# ESP8266.net
KiCad netlist of a schematic drawn in Altium Designer
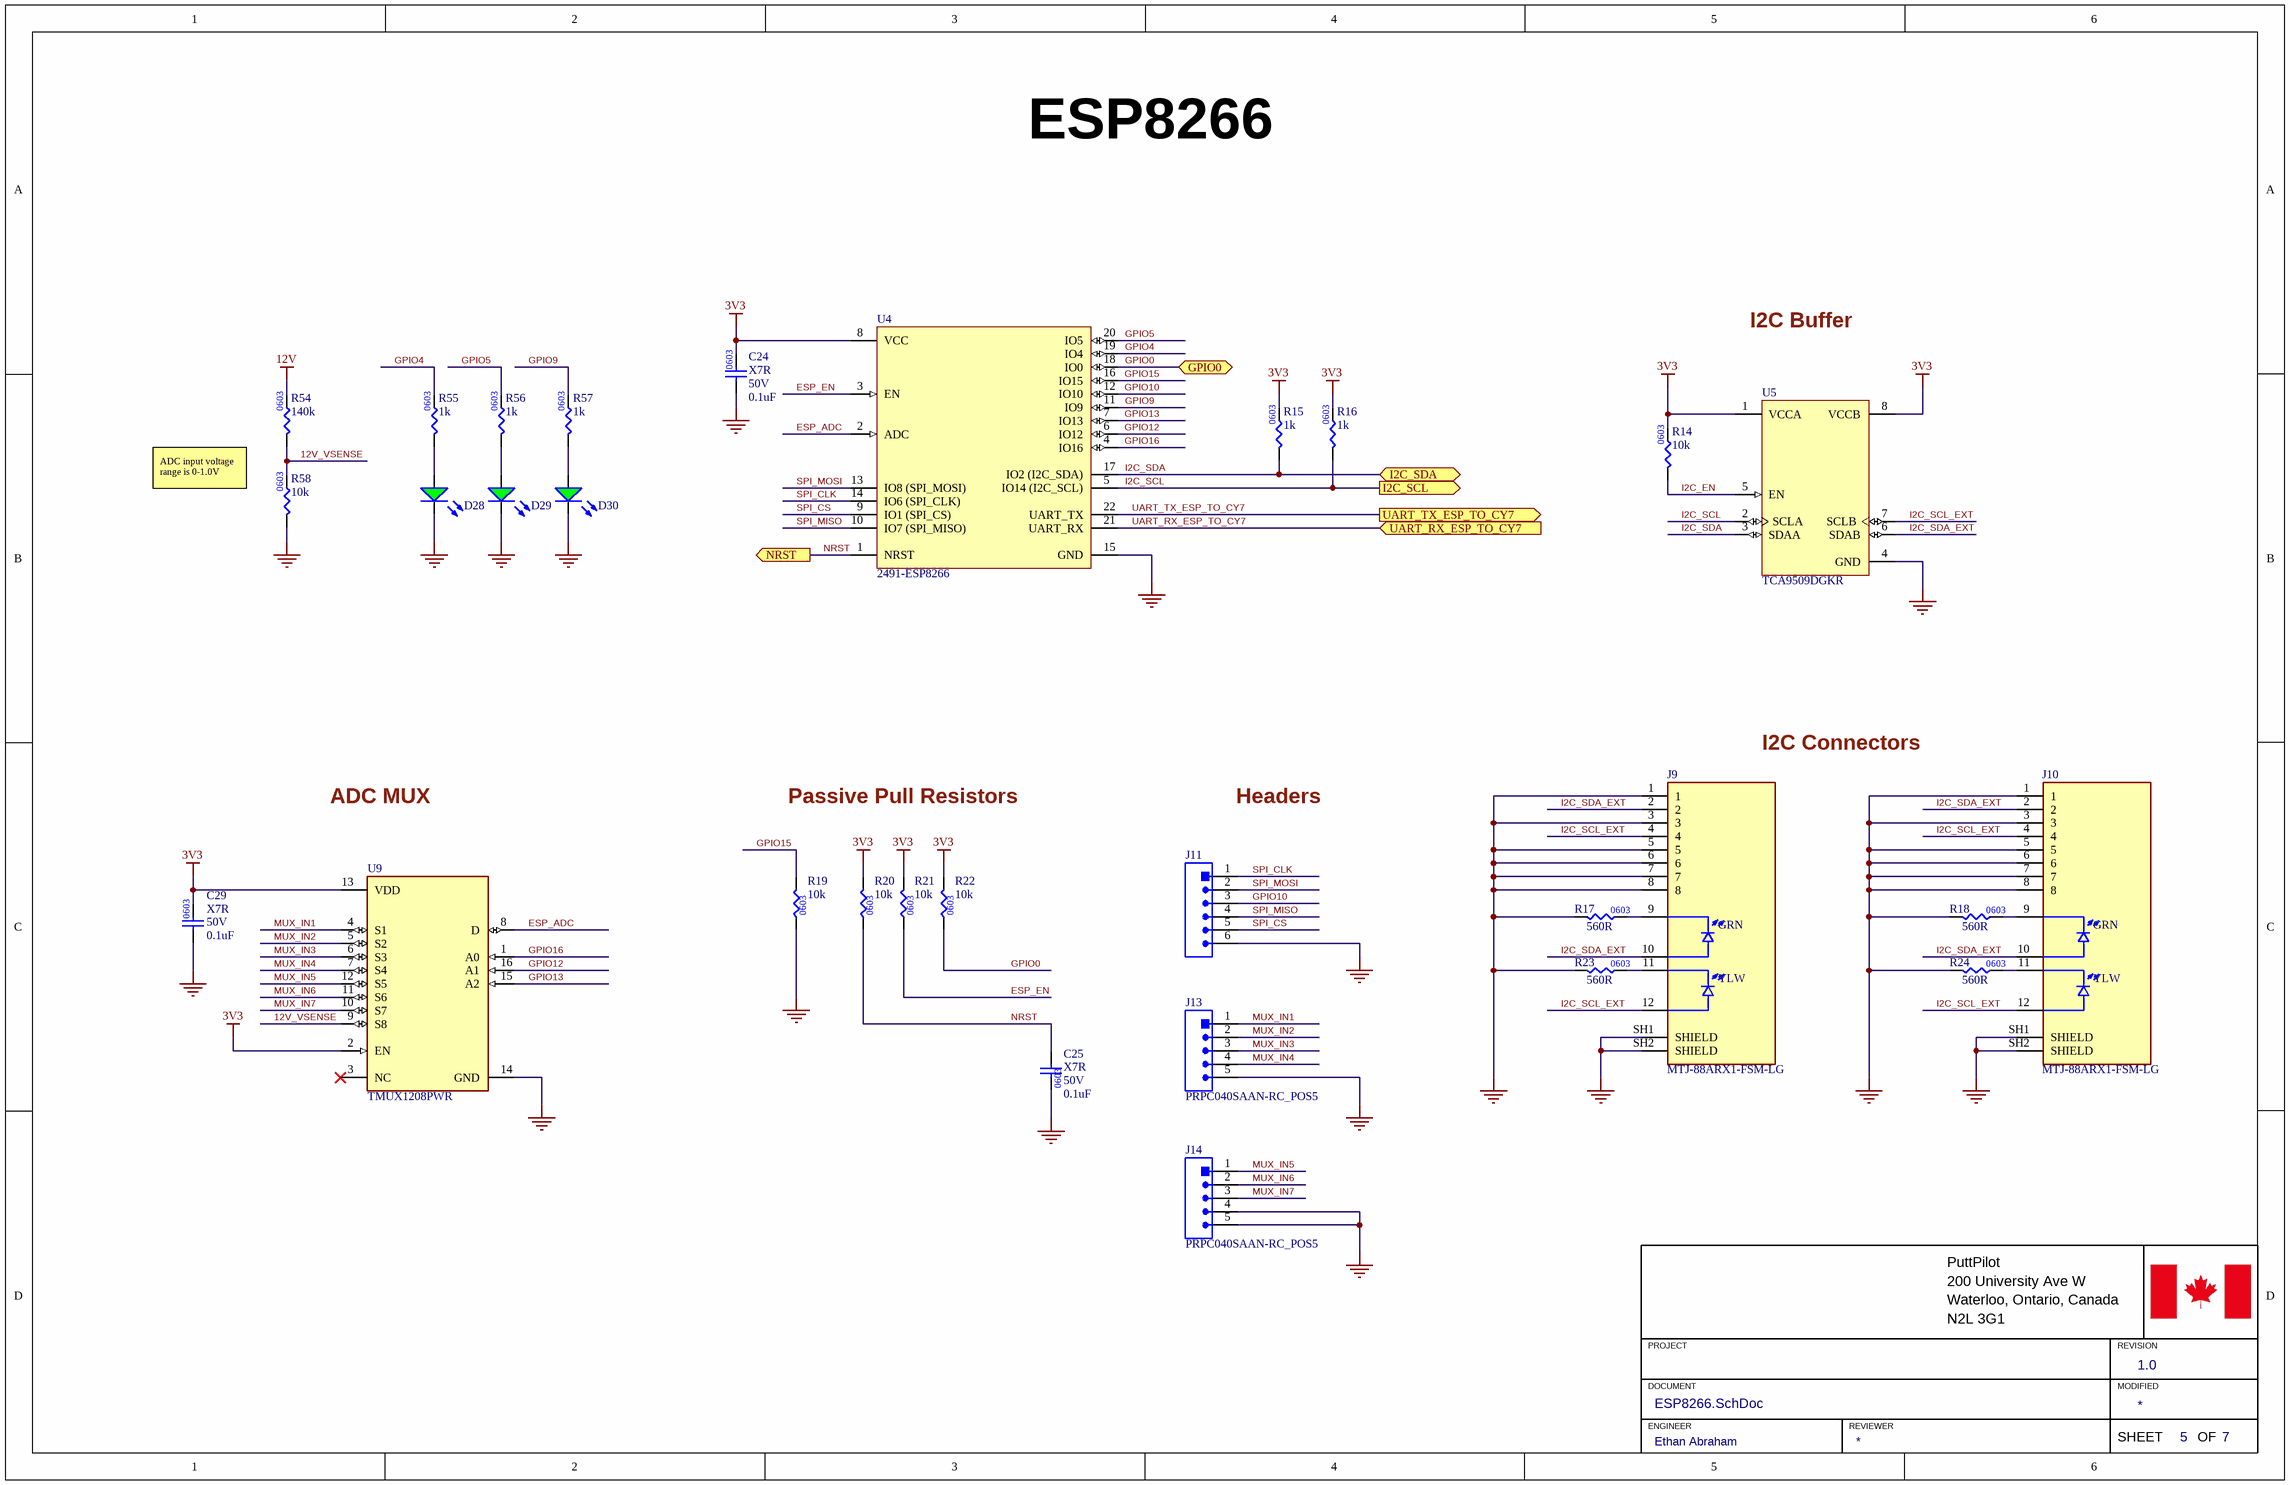
[diagram p0: ESP8266.SchDoc]

(export (version "E")
  (design (tool "Eeschema 10.0.6"))
  (components
    (comp (ref "C24")
      (value "GCJ188R71H104KA12D")
      (footprint ".CAP_0603")
      (description "CAP CER 0.1uF 50V X7R 0603")
      (fields
        (field (name "MANUFACTURER") "Murata")
        (field (name "TEMPERATURE CHARACTERISTICS CODE") "X7R")
        (field (name "RATED DC VOLTAGE (URDC)") "50V")
        (field (name "CAPACITANCE") "0.1uF")
      )
      (libsource (lib "PuttPilot") (part "GCJ188R71H104KA12D"))
    )
    (comp (ref "C25")
      (value "GCJ188R71H104KA12D")
      (footprint ".CAP_0603")
      (description "CAP CER 0.1uF 50V X7R 0603")
      (fields
        (field (name "MANUFACTURER") "Murata")
        (field (name "TEMPERATURE CHARACTERISTICS CODE") "X7R")
        (field (name "RATED DC VOLTAGE (URDC)") "50V")
        (field (name "CAPACITANCE") "0.1uF")
      )
      (libsource (lib "PuttPilot") (part "GCJ188R71H104KA12D"))
    )
    (comp (ref "C29")
      (value "GCJ188R71H104KA12D")
      (footprint ".CAP_0603")
      (description "CAP CER 0.1uF 50V X7R 0603")
      (fields
        (field (name "MANUFACTURER") "Murata")
        (field (name "TEMPERATURE CHARACTERISTICS CODE") "X7R")
        (field (name "RATED DC VOLTAGE (URDC)") "50V")
        (field (name "CAPACITANCE") "0.1uF")
      )
      (libsource (lib "PuttPilot") (part "GCJ188R71H104KA12D"))
    )
    (comp (ref "D28")
      (value "LTST-C191KGKT")
      (footprint ".LED_0603")
      (description "LED GREEN 2V 0603")
      (fields (field (name "MANUFACTURER") "Vishay Lite-On"))
      (libsource (lib "PuttPilot") (part "LTST-C191KGKT"))
    )
    (comp (ref "D29")
      (value "LTST-C191KGKT")
      (footprint ".LED_0603")
      (description "LED GREEN 2V 0603")
      (fields (field (name "MANUFACTURER") "Vishay Lite-On"))
      (libsource (lib "PuttPilot") (part "LTST-C191KGKT"))
    )
    (comp (ref "D30")
      (value "LTST-C191KGKT")
      (footprint ".LED_0603")
      (description "LED GREEN 2V 0603")
      (fields (field (name "MANUFACTURER") "Vishay Lite-On"))
      (libsource (lib "PuttPilot") (part "LTST-C191KGKT"))
    )
    (comp (ref "J9")
      (value "MTJ-88ARX1-FSM-LG")
      (footprint "MTJ-88ARX1-FSM-LG")
      (description "RJ45 JACK R/A SHIELDED")
      (fields (field (name "MANUFACTURER") "Adam Equipment"))
      (libsource (lib "PuttPilot") (part "MTJ-88ARX1-FSM-LG"))
    )
    (comp (ref "J10")
      (value "MTJ-88ARX1-FSM-LG")
      (footprint "MTJ-88ARX1-FSM-LG")
      (description "RJ45 JACK R/A SHIELDED")
      (fields (field (name "MANUFACTURER") "Adam Equipment"))
      (libsource (lib "PuttPilot") (part "MTJ-88ARX1-FSM-LG"))
    )
    (comp (ref "J11")
      (value "PRPC040SAAN-RC_POS6")
      (footprint "HEADER_6POS_2.54MM")
      (description "CONN HEADER VERT 6POS 2.54MM")
      (libsource (lib "PuttPilot") (part "PRPC040SAAN-RC_POS6"))
    )
    (comp (ref "J13")
      (value "PRPC040SAAN-RC_POS5")
      (footprint "HEADER_5POS_2.54MM")
      (description "CONN HEADER VERT 5POS 2.54MM")
      (libsource (lib "PuttPilot") (part "PRPC040SAAN-RC_POS5"))
    )
    (comp (ref "J14")
      (value "PRPC040SAAN-RC_POS5")
      (footprint "HEADER_5POS_2.54MM")
      (description "CONN HEADER VERT 5POS 2.54MM")
      (libsource (lib "PuttPilot") (part "PRPC040SAAN-RC_POS5"))
    )
    (comp (ref "R14")
      (value "RC0603FR-0710KL")
      (footprint ".RES_0603")
      (description "RES 10K OHM 0603")
      (fields
        (field (name "MANUFACTURER") "Yageo")
        (field (name "TOLERANCE") "1%")
        (field (name "RESISTANCE") "10k")
      )
      (libsource (lib "PuttPilot") (part "RC0603FR-0710KL"))
    )
    (comp (ref "R15")
      (value "RC0603FR-071KL")
      (footprint ".RES_0603")
      (description "RES 1K OHM 0603")
      (fields
        (field (name "MANUFACTURER") "Yageo")
        (field (name "TOLERANCE") "1%")
        (field (name "RESISTANCE") "1k")
      )
      (libsource (lib "PuttPilot") (part "RC0603FR-071KL"))
    )
    (comp (ref "R16")
      (value "RC0603FR-071KL")
      (footprint ".RES_0603")
      (description "RES 1K OHM 0603")
      (fields
        (field (name "MANUFACTURER") "Yageo")
        (field (name "TOLERANCE") "1%")
        (field (name "RESISTANCE") "1k")
      )
      (libsource (lib "PuttPilot") (part "RC0603FR-071KL"))
    )
    (comp (ref "R17")
      (value "RC0603FR-07560RL")
      (footprint ".RES_0603")
      (description "RES 560 OHM 0603")
      (fields
        (field (name "MANUFACTURER") "Yageo")
        (field (name "TOLERANCE") "1%")
        (field (name "RESISTANCE") "560R")
      )
      (libsource (lib "PuttPilot") (part "RC0603FR-07560RL"))
    )
    (comp (ref "R18")
      (value "RC0603FR-07560RL")
      (footprint ".RES_0603")
      (description "RES 560 OHM 0603")
      (fields
        (field (name "MANUFACTURER") "Yageo")
        (field (name "TOLERANCE") "1%")
        (field (name "RESISTANCE") "560R")
      )
      (libsource (lib "PuttPilot") (part "RC0603FR-07560RL"))
    )
    (comp (ref "R19")
      (value "RC0603FR-0710KL")
      (footprint ".RES_0603")
      (description "RES 10K OHM 0603")
      (fields
        (field (name "MANUFACTURER") "Yageo")
        (field (name "TOLERANCE") "1%")
        (field (name "RESISTANCE") "10k")
      )
      (libsource (lib "PuttPilot") (part "RC0603FR-0710KL"))
    )
    (comp (ref "R20")
      (value "RC0603FR-0710KL")
      (footprint ".RES_0603")
      (description "RES 10K OHM 0603")
      (fields
        (field (name "MANUFACTURER") "Yageo")
        (field (name "TOLERANCE") "1%")
        (field (name "RESISTANCE") "10k")
      )
      (libsource (lib "PuttPilot") (part "RC0603FR-0710KL"))
    )
    (comp (ref "R21")
      (value "RC0603FR-0710KL")
      (footprint ".RES_0603")
      (description "RES 10K OHM 0603")
      (fields
        (field (name "MANUFACTURER") "Yageo")
        (field (name "TOLERANCE") "1%")
        (field (name "RESISTANCE") "10k")
      )
      (libsource (lib "PuttPilot") (part "RC0603FR-0710KL"))
    )
    (comp (ref "R22")
      (value "RC0603FR-0710KL")
      (footprint ".RES_0603")
      (description "RES 10K OHM 0603")
      (fields
        (field (name "MANUFACTURER") "Yageo")
        (field (name "TOLERANCE") "1%")
        (field (name "RESISTANCE") "10k")
      )
      (libsource (lib "PuttPilot") (part "RC0603FR-0710KL"))
    )
    (comp (ref "R23")
      (value "RC0603FR-07560RL")
      (footprint ".RES_0603")
      (description "RES 560 OHM 0603")
      (fields
        (field (name "MANUFACTURER") "Yageo")
        (field (name "TOLERANCE") "1%")
        (field (name "RESISTANCE") "560R")
      )
      (libsource (lib "PuttPilot") (part "RC0603FR-07560RL"))
    )
    (comp (ref "R24")
      (value "RC0603FR-07560RL")
      (footprint ".RES_0603")
      (description "RES 560 OHM 0603")
      (fields
        (field (name "MANUFACTURER") "Yageo")
        (field (name "TOLERANCE") "1%")
        (field (name "RESISTANCE") "560R")
      )
      (libsource (lib "PuttPilot") (part "RC0603FR-07560RL"))
    )
    (comp (ref "R54")
      (value "RC0603FR-07140KL")
      (footprint ".RES_0603")
      (description "RES 140K OHM 0603")
      (fields
        (field (name "MANUFACTURER") "Yageo")
        (field (name "TOLERANCE") "1%")
        (field (name "RESISTANCE") "140k")
      )
      (libsource (lib "PuttPilot") (part "RC0603FR-07140KL"))
    )
    (comp (ref "R55")
      (value "RC0603FR-071KL")
      (footprint ".RES_0603")
      (description "RES 1K OHM 0603")
      (fields
        (field (name "MANUFACTURER") "Yageo")
        (field (name "TOLERANCE") "1%")
        (field (name "RESISTANCE") "1k")
      )
      (libsource (lib "PuttPilot") (part "RC0603FR-071KL"))
    )
    (comp (ref "R56")
      (value "RC0603FR-071KL")
      (footprint ".RES_0603")
      (description "RES 1K OHM 0603")
      (fields
        (field (name "MANUFACTURER") "Yageo")
        (field (name "TOLERANCE") "1%")
        (field (name "RESISTANCE") "1k")
      )
      (libsource (lib "PuttPilot") (part "RC0603FR-071KL"))
    )
    (comp (ref "R57")
      (value "RC0603FR-071KL")
      (footprint ".RES_0603")
      (description "RES 1K OHM 0603")
      (fields
        (field (name "MANUFACTURER") "Yageo")
        (field (name "TOLERANCE") "1%")
        (field (name "RESISTANCE") "1k")
      )
      (libsource (lib "PuttPilot") (part "RC0603FR-071KL"))
    )
    (comp (ref "R58")
      (value "RC0603FR-0710KL")
      (footprint ".RES_0603")
      (description "RES 10K OHM 0603")
      (fields
        (field (name "MANUFACTURER") "Yageo")
        (field (name "TOLERANCE") "1%")
        (field (name "RESISTANCE") "10k")
      )
      (libsource (lib "PuttPilot") (part "RC0603FR-0710KL"))
    )
    (comp (ref "U4")
      (value "2491-ESP8266")
      (footprint "2491-ESP8266")
      (description "ESP8266 + Trace Antenna, 4MB Flash")
      (libsource (lib "PuttPilot") (part "2491-ESP8266"))
    )
    (comp (ref "U5")
      (value "TCA9509DGKR")
      (footprint "TCA9509DGKR")
      (description "I2C BUFFER IC")
      (fields (field (name "MANUFACTURER") "Texas Instruments"))
      (libsource (lib "PuttPilot") (part "TCA9509DGKR"))
    )
    (comp (ref "U9")
      (value "TMUX1208PWR")
      (footprint "TMUX1208")
      (description "Single-Ended Multiplexer, 1 Func, 8 Channel, CMOS, PDSO16")
      (fields (field (name "MANUFACTURER") "Texas Instruments"))
      (libsource (lib "PuttPilot") (part "TMUX1208PWR"))
    )
  )
  (nets
    (net (code "1") (name "/12V_VSENSE") (class "Default")
      (node (ref "R54") (pin "1") (pinfunction "1_1") (pintype "passive"))
      (node (ref "R58") (pin "2") (pinfunction "2_2") (pintype "passive"))
      (node (ref "U9") (pin "9") (pinfunction "S8_9") (pintype "bidirectional"))
    )
    (net (code "2") (name "/ESP_ADC") (class "Default")
      (node (ref "U4") (pin "2") (pinfunction "ADC_2") (pintype "input"))
      (node (ref "U9") (pin "8") (pinfunction "D_8") (pintype "bidirectional"))
    )
    (net (code "3") (name "/ESP_EN") (class "Default")
      (node (ref "R21") (pin "1") (pinfunction "1_1") (pintype "passive"))
      (node (ref "U4") (pin "3") (pinfunction "EN_3") (pintype "input"))
    )
    (net (code "4") (name "/GPIO0") (class "Default")
      (node (ref "R22") (pin "1") (pinfunction "1_1") (pintype "passive"))
      (node (ref "U4") (pin "18") (pinfunction "IO0_18") (pintype "bidirectional"))
    )
    (net (code "5") (name "/GPIO4") (class "Default")
      (node (ref "R55") (pin "2") (pinfunction "2_2") (pintype "passive"))
      (node (ref "U4") (pin "19") (pinfunction "IO4_19") (pintype "bidirectional"))
    )
    (net (code "6") (name "/GPIO5") (class "Default")
      (node (ref "R56") (pin "2") (pinfunction "2_2") (pintype "passive"))
      (node (ref "U4") (pin "20") (pinfunction "IO5_20") (pintype "bidirectional"))
    )
    (net (code "7") (name "/GPIO9") (class "Default")
      (node (ref "R57") (pin "2") (pinfunction "2_2") (pintype "passive"))
      (node (ref "U4") (pin "11") (pinfunction "IO9_11") (pintype "bidirectional"))
    )
    (net (code "8") (name "/GPIO10") (class "Default")
      (node (ref "J11") (pin "3") (pinfunction "3_3") (pintype "passive"))
      (node (ref "U4") (pin "12") (pinfunction "IO10_12") (pintype "bidirectional"))
    )
    (net (code "9") (name "/GPIO12") (class "Default")
      (node (ref "U4") (pin "6") (pinfunction "IO12_6") (pintype "bidirectional"))
      (node (ref "U9") (pin "16") (pinfunction "A1_16") (pintype "input"))
    )
    (net (code "10") (name "/GPIO13") (class "Default")
      (node (ref "U4") (pin "7") (pinfunction "IO13_7") (pintype "bidirectional"))
      (node (ref "U9") (pin "15") (pinfunction "A2_15") (pintype "input"))
    )
    (net (code "11") (name "/GPIO15") (class "Default")
      (node (ref "R19") (pin "2") (pinfunction "2_2") (pintype "passive"))
      (node (ref "U4") (pin "16") (pinfunction "IO15_16") (pintype "bidirectional"))
    )
    (net (code "12") (name "/GPIO16") (class "Default")
      (node (ref "U4") (pin "4") (pinfunction "IO16_4") (pintype "bidirectional"))
      (node (ref "U9") (pin "1") (pinfunction "A0_1") (pintype "input"))
    )
    (net (code "13") (name "/I2C_EN") (class "Default")
      (node (ref "R14") (pin "1") (pinfunction "1_1") (pintype "passive"))
      (node (ref "U5") (pin "5") (pinfunction "EN_5") (pintype "input"))
    )
    (net (code "14") (name "/I2C_SCL") (class "Default")
      (node (ref "R16") (pin "1") (pinfunction "1_1") (pintype "passive"))
      (node (ref "U4") (pin "5") (pinfunction "IO14_(I2C_SCL)_5") (pintype "passive"))
      (node (ref "U5") (pin "2") (pinfunction "SCLA_2") (pintype "bidirectional"))
    )
    (net (code "15") (name "/I2C_SCL_EXT") (class "Default")
      (node (ref "J10") (pin "12") (pinfunction "12_12") (pintype "passive"))
      (node (ref "J10") (pin "4") (pinfunction "4_4") (pintype "passive"))
      (node (ref "J9") (pin "12") (pinfunction "12_12") (pintype "passive"))
      (node (ref "J9") (pin "4") (pinfunction "4_4") (pintype "passive"))
      (node (ref "U5") (pin "7") (pinfunction "SCLB_7") (pintype "bidirectional"))
    )
    (net (code "16") (name "/I2C_SDA") (class "Default")
      (node (ref "R15") (pin "1") (pinfunction "1_1") (pintype "passive"))
      (node (ref "U4") (pin "17") (pinfunction "IO2_(I2C_SDA)_17") (pintype "passive"))
      (node (ref "U5") (pin "3") (pinfunction "SDAA_3") (pintype "bidirectional"))
    )
    (net (code "17") (name "/I2C_SDA_EXT") (class "Default")
      (node (ref "J10") (pin "10") (pinfunction "10_10") (pintype "passive"))
      (node (ref "J10") (pin "2") (pinfunction "2_2") (pintype "passive"))
      (node (ref "J9") (pin "10") (pinfunction "10_10") (pintype "passive"))
      (node (ref "J9") (pin "2") (pinfunction "2_2") (pintype "passive"))
      (node (ref "U5") (pin "6") (pinfunction "SDAB_6") (pintype "bidirectional"))
    )
    (net (code "18") (name "/MUX_IN1") (class "Default")
      (node (ref "J13") (pin "1") (pinfunction "1_1") (pintype "passive"))
      (node (ref "U9") (pin "4") (pinfunction "S1_4") (pintype "bidirectional"))
    )
    (net (code "19") (name "/MUX_IN2") (class "Default")
      (node (ref "J13") (pin "2") (pinfunction "2_2") (pintype "passive"))
      (node (ref "U9") (pin "5") (pinfunction "S2_5") (pintype "bidirectional"))
    )
    (net (code "20") (name "/MUX_IN3") (class "Default")
      (node (ref "J13") (pin "3") (pinfunction "3_3") (pintype "passive"))
      (node (ref "U9") (pin "6") (pinfunction "S3_6") (pintype "bidirectional"))
    )
    (net (code "21") (name "/MUX_IN4") (class "Default")
      (node (ref "J13") (pin "4") (pinfunction "4_4") (pintype "passive"))
      (node (ref "U9") (pin "7") (pinfunction "S4_7") (pintype "bidirectional"))
    )
    (net (code "22") (name "/MUX_IN5") (class "Default")
      (node (ref "J14") (pin "1") (pinfunction "1_1") (pintype "passive"))
      (node (ref "U9") (pin "12") (pinfunction "S5_12") (pintype "bidirectional"))
    )
    (net (code "23") (name "/MUX_IN6") (class "Default")
      (node (ref "J14") (pin "2") (pinfunction "2_2") (pintype "passive"))
      (node (ref "U9") (pin "11") (pinfunction "S6_11") (pintype "bidirectional"))
    )
    (net (code "24") (name "/MUX_IN7") (class "Default")
      (node (ref "J14") (pin "3") (pinfunction "3_3") (pintype "passive"))
      (node (ref "U9") (pin "10") (pinfunction "S7_10") (pintype "bidirectional"))
    )
    (net (code "25") (name "/NRST") (class "Default")
      (node (ref "C25") (pin "2") (pinfunction "2_2") (pintype "passive"))
      (node (ref "R20") (pin "1") (pinfunction "1_1") (pintype "passive"))
      (node (ref "U4") (pin "1") (pinfunction "NRST_1") (pintype "passive"))
    )
    (net (code "26") (name "/SPI_CLK") (class "Default")
      (node (ref "J11") (pin "1") (pinfunction "1_1") (pintype "passive"))
      (node (ref "U4") (pin "14") (pinfunction "IO6_(SPI_CLK)_14") (pintype "passive"))
    )
    (net (code "27") (name "/SPI_CS") (class "Default")
      (node (ref "J11") (pin "5") (pinfunction "5_5") (pintype "passive"))
      (node (ref "U4") (pin "9") (pinfunction "IO1_(SPI_CS)_9") (pintype "passive"))
    )
    (net (code "28") (name "/SPI_MISO") (class "Default")
      (node (ref "J11") (pin "4") (pinfunction "4_4") (pintype "passive"))
      (node (ref "U4") (pin "10") (pinfunction "IO7_(SPI_MISO)_10") (pintype "passive"))
    )
    (net (code "29") (name "/SPI_MOSI") (class "Default")
      (node (ref "J11") (pin "2") (pinfunction "2_2") (pintype "passive"))
      (node (ref "U4") (pin "13") (pinfunction "IO8_(SPI_MOSI)_13") (pintype "passive"))
    )
    (net (code "30") (name "/UART_RX_ESP_TO_CY7") (class "Default")
      (node (ref "U4") (pin "21") (pinfunction "UART_RX_21") (pintype "passive"))
    )
    (net (code "31") (name "/UART_TX_ESP_TO_CY7") (class "Default")
      (node (ref "U4") (pin "22") (pinfunction "UART_TX_22") (pintype "passive"))
    )
    (net (code "32") (name "3V3") (class "Default")
      (node (ref "C24") (pin "2") (pinfunction "2_2") (pintype "passive"))
      (node (ref "C29") (pin "2") (pinfunction "2_2") (pintype "passive"))
      (node (ref "R14") (pin "2") (pinfunction "2_2") (pintype "passive"))
      (node (ref "R15") (pin "2") (pinfunction "2_2") (pintype "passive"))
      (node (ref "R16") (pin "2") (pinfunction "2_2") (pintype "passive"))
      (node (ref "R20") (pin "2") (pinfunction "2_2") (pintype "passive"))
      (node (ref "R21") (pin "2") (pinfunction "2_2") (pintype "passive"))
      (node (ref "R22") (pin "2") (pinfunction "2_2") (pintype "passive"))
      (node (ref "U4") (pin "8") (pinfunction "VCC_8") (pintype "power_in"))
      (node (ref "U5") (pin "1") (pinfunction "VCCA_1") (pintype "power_in"))
      (node (ref "U5") (pin "8") (pinfunction "VCCB_8") (pintype "power_in"))
      (node (ref "U9") (pin "13") (pinfunction "VDD_13") (pintype "power_in"))
      (node (ref "U9") (pin "2") (pinfunction "EN_2") (pintype "input"))
    )
    (net (code "33") (name "12V") (class "Default")
      (node (ref "R54") (pin "2") (pinfunction "2_2") (pintype "passive"))
    )
    (net (code "34") (name "GND") (class "Default")
      (node (ref "C24") (pin "1") (pinfunction "1_1") (pintype "passive"))
      (node (ref "C25") (pin "1") (pinfunction "1_1") (pintype "passive"))
      (node (ref "C29") (pin "1") (pinfunction "1_1") (pintype "passive"))
      (node (ref "D28") (pin "2") (pinfunction "K_2") (pintype "passive"))
      (node (ref "D29") (pin "2") (pinfunction "K_2") (pintype "passive"))
      (node (ref "D30") (pin "2") (pinfunction "K_2") (pintype "passive"))
      (node (ref "J10") (pin "1") (pinfunction "1_1") (pintype "passive"))
      (node (ref "J10") (pin "3") (pinfunction "3_3") (pintype "passive"))
      (node (ref "J10") (pin "5") (pinfunction "5_5") (pintype "passive"))
      (node (ref "J10") (pin "6") (pinfunction "6_6") (pintype "passive"))
      (node (ref "J10") (pin "7") (pinfunction "7_7") (pintype "passive"))
      (node (ref "J10") (pin "8") (pinfunction "8_8") (pintype "passive"))
      (node (ref "J10") (pin "SH1") (pinfunction "SHIELD_SH1") (pintype "passive"))
      (node (ref "J10") (pin "SH2") (pinfunction "SHIELD_SH2") (pintype "passive"))
      (node (ref "J11") (pin "6") (pinfunction "6_6") (pintype "passive"))
      (node (ref "J13") (pin "5") (pinfunction "5_5") (pintype "passive"))
      (node (ref "J14") (pin "4") (pinfunction "4_4") (pintype "passive"))
      (node (ref "J14") (pin "5") (pinfunction "5_5") (pintype "passive"))
      (node (ref "J9") (pin "1") (pinfunction "1_1") (pintype "passive"))
      (node (ref "J9") (pin "3") (pinfunction "3_3") (pintype "passive"))
      (node (ref "J9") (pin "5") (pinfunction "5_5") (pintype "passive"))
      (node (ref "J9") (pin "6") (pinfunction "6_6") (pintype "passive"))
      (node (ref "J9") (pin "7") (pinfunction "7_7") (pintype "passive"))
      (node (ref "J9") (pin "8") (pinfunction "8_8") (pintype "passive"))
      (node (ref "J9") (pin "SH1") (pinfunction "SHIELD_SH1") (pintype "passive"))
      (node (ref "J9") (pin "SH2") (pinfunction "SHIELD_SH2") (pintype "passive"))
      (node (ref "R17") (pin "1") (pinfunction "1_1") (pintype "passive"))
      (node (ref "R18") (pin "1") (pinfunction "1_1") (pintype "passive"))
      (node (ref "R19") (pin "1") (pinfunction "1_1") (pintype "passive"))
      (node (ref "R23") (pin "1") (pinfunction "1_1") (pintype "passive"))
      (node (ref "R24") (pin "1") (pinfunction "1_1") (pintype "passive"))
      (node (ref "R58") (pin "1") (pinfunction "1_1") (pintype "passive"))
      (node (ref "U4") (pin "15") (pinfunction "GND_15") (pintype "power_in"))
      (node (ref "U5") (pin "4") (pinfunction "GND_4") (pintype "power_in"))
      (node (ref "U9") (pin "14") (pinfunction "GND_14") (pintype "power_in"))
    )
    (net (code "35") (name "Net-(D28-A)") (class "Default")
      (node (ref "D28") (pin "1") (pinfunction "A_1") (pintype "passive"))
      (node (ref "R55") (pin "1") (pinfunction "1_1") (pintype "passive"))
    )
    (net (code "36") (name "Net-(D29-A)") (class "Default")
      (node (ref "D29") (pin "1") (pinfunction "A_1") (pintype "passive"))
      (node (ref "R56") (pin "1") (pinfunction "1_1") (pintype "passive"))
    )
    (net (code "37") (name "Net-(D30-A)") (class "Default")
      (node (ref "D30") (pin "1") (pinfunction "A_1") (pintype "passive"))
      (node (ref "R57") (pin "1") (pinfunction "1_1") (pintype "passive"))
    )
    (net (code "38") (name "Net-(J9-Pad9)") (class "Default")
      (node (ref "J9") (pin "9") (pinfunction "9_9") (pintype "passive"))
      (node (ref "R17") (pin "2") (pinfunction "2_2") (pintype "passive"))
    )
    (net (code "39") (name "Net-(J9-Pad11)") (class "Default")
      (node (ref "J9") (pin "11") (pinfunction "11_11") (pintype "passive"))
      (node (ref "R23") (pin "2") (pinfunction "2_2") (pintype "passive"))
    )
    (net (code "40") (name "Net-(J10-Pad9)") (class "Default")
      (node (ref "J10") (pin "9") (pinfunction "9_9") (pintype "passive"))
      (node (ref "R18") (pin "2") (pinfunction "2_2") (pintype "passive"))
    )
    (net (code "41") (name "Net-(J10-Pad11)") (class "Default")
      (node (ref "J10") (pin "11") (pinfunction "11_11") (pintype "passive"))
      (node (ref "R24") (pin "2") (pinfunction "2_2") (pintype "passive"))
    )
    (net (code "42") (name "unconnected-(U9-NC-Pad3)") (class "Default")
      (node (ref "U9") (pin "3") (pinfunction "NC_3") (pintype "passive+no_connect"))
    )
  )
)
